# 04_DEBUG_DISPLAY.net
KiCad netlist of a schematic drawn in Altium Designer
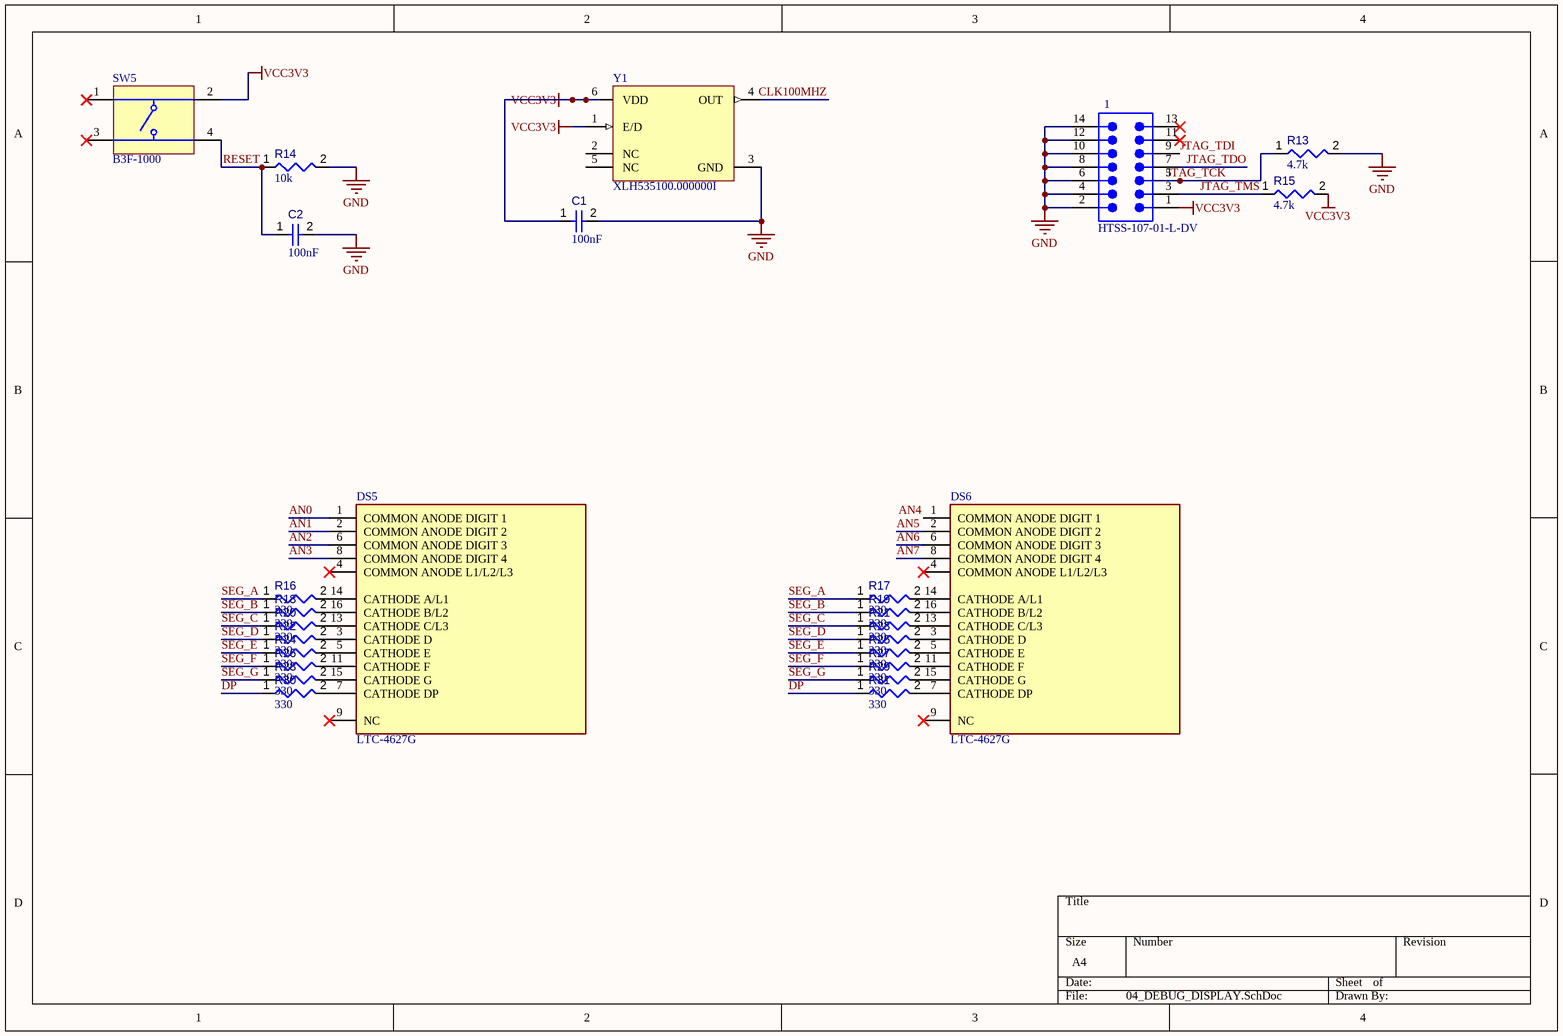
[diagram p0: 04_DEBUG_DISPLAY.SchDoc]

(export (version "E")
  (design (tool "Eeschema 10.0.6"))
  (components
    (comp (ref "1")
      (value "HTSS-107-01-L-DV")
      (footprint "SMTC-HTSS-107-01-X-DV")
      (fields (field (name "MANUFACTURER") "Samtec"))
      (libsource (lib "Altium Content Vault") (part "SMTC-HTSS-107-01-X-DV"))
    )
    (comp (ref "C1")
      (value "100nF")
      (footprint "CAPC0402(1005)60_L")
      (description "Chip Capacitor, 100nF +/-20%, 25V, 0402, Thickness 0.6 mm")
      (fields (field (name "TOLERANCE") "10%") (field (name "Comment") "Capacitor 100nF +/-20% 25V 0402"))
      (libsource (lib "Md-azadul Islam") (part "CAP-NP-2"))
    )
    (comp (ref "C2")
      (value "100nF")
      (footprint "CAPC0402(1005)60_L")
      (description "Chip Capacitor, 100nF +/-20%, 25V, 0402, Thickness 0.6 mm")
      (fields (field (name "TOLERANCE") "10%") (field (name "Comment") "Capacitor 100nF +/-20% 25V 0402"))
      (libsource (lib "Md-azadul Islam") (part "CAP-NP-2"))
    )
    (comp (ref "DS5")
      (value "LTC-4627G")
      (footprint "FP-LTC-4627G-MFG")
      (description "LED 7-SEG 4DIGIT GRN 0.4\" CA")
      (fields
        (field (name "OCTOPART") "https://octopart.com/ltc-4627g-lite-on-8442722")
        (field (name "MANUFACTURER") "Lite-On")
      )
      (libsource (lib "Altium Content Vault") (part "4d055b40ff5d7e2a8d2cf02d3223e38"))
    )
    (comp (ref "DS6")
      (value "LTC-4627G")
      (footprint "FP-LTC-4627G-MFG")
      (description "LED 7-SEG 4DIGIT GRN 0.4\" CA")
      (fields
        (field (name "OCTOPART") "https://octopart.com/ltc-4627g-lite-on-8442722")
        (field (name "MANUFACTURER") "Lite-On")
      )
      (libsource (lib "Altium Content Vault") (part "4d055b40ff5d7e2a8d2cf02d3223e38"))
    )
    (comp (ref "R13")
      (value "4.7k")
      (footprint "RESC0402(1005)_L")
      (description "Chip Resistor, 4,7 kOhms, +/-1 %, 63 mW, -55 to 155 degC, 0402")
      (fields (field (name "POWER") "63mW") (field (name "TOLERANCE") "1%"))
      (libsource (lib "Md-azadul Islam") (part "RES-2"))
    )
    (comp (ref "R14")
      (value "10k")
      (footprint "RESC0402(1005)_L")
      (description "10K 0.063W 1% 0402 (1005 Metric)  SMD")
      (fields (field (name "POWER") "63mW") (field (name "TOLERANCE") "1%"))
      (libsource (lib "Md-azadul Islam") (part "10KR2F"))
    )
    (comp (ref "R15")
      (value "4.7k")
      (footprint "RESC0402(1005)_L")
      (description "Chip Resistor, 4,7 kOhms, +/-1 %, 63 mW, -55 to 155 degC, 0402")
      (fields (field (name "POWER") "63mW") (field (name "TOLERANCE") "1%"))
      (libsource (lib "Md-azadul Islam") (part "RES-2"))
    )
    (comp (ref "R16")
      (value "330")
      (footprint "RESC0402(1005)_L")
      (description "330R 0.063W 5% 0402 (1005 Metric)  SMD")
      (fields (field (name "TOLERANCE") "5%") (field (name "POWER") "63mW"))
      (libsource (lib "Md-azadul Islam") (part "330R2J"))
    )
    (comp (ref "R17")
      (value "330")
      (footprint "RESC0402(1005)_L")
      (description "330R 0.063W 5% 0402 (1005 Metric)  SMD")
      (fields (field (name "TOLERANCE") "5%") (field (name "POWER") "63mW"))
      (libsource (lib "Md-azadul Islam") (part "330R2J"))
    )
    (comp (ref "R18")
      (value "330")
      (footprint "RESC0402(1005)_L")
      (description "330R 0.063W 5% 0402 (1005 Metric)  SMD")
      (fields (field (name "TOLERANCE") "5%") (field (name "POWER") "63mW"))
      (libsource (lib "Md-azadul Islam") (part "330R2J"))
    )
    (comp (ref "R19")
      (value "330")
      (footprint "RESC0402(1005)_L")
      (description "330R 0.063W 5% 0402 (1005 Metric)  SMD")
      (fields (field (name "TOLERANCE") "5%") (field (name "POWER") "63mW"))
      (libsource (lib "Md-azadul Islam") (part "330R2J"))
    )
    (comp (ref "R20")
      (value "330")
      (footprint "RESC0402(1005)_L")
      (description "330R 0.063W 5% 0402 (1005 Metric)  SMD")
      (fields (field (name "TOLERANCE") "5%") (field (name "POWER") "63mW"))
      (libsource (lib "Md-azadul Islam") (part "330R2J"))
    )
    (comp (ref "R21")
      (value "330")
      (footprint "RESC0402(1005)_L")
      (description "330R 0.063W 5% 0402 (1005 Metric)  SMD")
      (fields (field (name "TOLERANCE") "5%") (field (name "POWER") "63mW"))
      (libsource (lib "Md-azadul Islam") (part "330R2J"))
    )
    (comp (ref "R22")
      (value "330")
      (footprint "RESC0402(1005)_L")
      (description "330R 0.063W 5% 0402 (1005 Metric)  SMD")
      (fields (field (name "TOLERANCE") "5%") (field (name "POWER") "63mW"))
      (libsource (lib "Md-azadul Islam") (part "330R2J"))
    )
    (comp (ref "R23")
      (value "330")
      (footprint "RESC0402(1005)_L")
      (description "330R 0.063W 5% 0402 (1005 Metric)  SMD")
      (fields (field (name "TOLERANCE") "5%") (field (name "POWER") "63mW"))
      (libsource (lib "Md-azadul Islam") (part "330R2J"))
    )
    (comp (ref "R24")
      (value "330")
      (footprint "RESC0402(1005)_L")
      (description "330R 0.063W 5% 0402 (1005 Metric)  SMD")
      (fields (field (name "TOLERANCE") "5%") (field (name "POWER") "63mW"))
      (libsource (lib "Md-azadul Islam") (part "330R2J"))
    )
    (comp (ref "R25")
      (value "330")
      (footprint "RESC0402(1005)_L")
      (description "330R 0.063W 5% 0402 (1005 Metric)  SMD")
      (fields (field (name "TOLERANCE") "5%") (field (name "POWER") "63mW"))
      (libsource (lib "Md-azadul Islam") (part "330R2J"))
    )
    (comp (ref "R26")
      (value "330")
      (footprint "RESC0402(1005)_L")
      (description "330R 0.063W 5% 0402 (1005 Metric)  SMD")
      (fields (field (name "TOLERANCE") "5%") (field (name "POWER") "63mW"))
      (libsource (lib "Md-azadul Islam") (part "330R2J"))
    )
    (comp (ref "R27")
      (value "330")
      (footprint "RESC0402(1005)_L")
      (description "330R 0.063W 5% 0402 (1005 Metric)  SMD")
      (fields (field (name "TOLERANCE") "5%") (field (name "POWER") "63mW"))
      (libsource (lib "Md-azadul Islam") (part "330R2J"))
    )
    (comp (ref "R28")
      (value "330")
      (footprint "RESC0402(1005)_L")
      (description "330R 0.063W 5% 0402 (1005 Metric)  SMD")
      (fields (field (name "TOLERANCE") "5%") (field (name "POWER") "63mW"))
      (libsource (lib "Md-azadul Islam") (part "330R2J"))
    )
    (comp (ref "R29")
      (value "330")
      (footprint "RESC0402(1005)_L")
      (description "330R 0.063W 5% 0402 (1005 Metric)  SMD")
      (fields (field (name "TOLERANCE") "5%") (field (name "POWER") "63mW"))
      (libsource (lib "Md-azadul Islam") (part "330R2J"))
    )
    (comp (ref "R30")
      (value "330")
      (footprint "RESC0402(1005)_L")
      (description "330R 0.063W 5% 0402 (1005 Metric)  SMD")
      (fields (field (name "TOLERANCE") "5%") (field (name "POWER") "63mW"))
      (libsource (lib "Md-azadul Islam") (part "330R2J"))
    )
    (comp (ref "R31")
      (value "330")
      (footprint "RESC0402(1005)_L")
      (description "330R 0.063W 5% 0402 (1005 Metric)  SMD")
      (fields (field (name "TOLERANCE") "5%") (field (name "POWER") "63mW"))
      (libsource (lib "Md-azadul Islam") (part "330R2J"))
    )
    (comp (ref "SW5")
      (value "B3F-1000")
      (footprint "OMRON-B3F-1000-4_V")
      (description "Tactile Switch, SPST-NO, 0.05 A, 24 V, -25 to 70 degC, 4-Pin THD, RoHS, Bulk")
      (fields (field (name "MANUFACTURER") "Omron Electronic Components"))
      (libsource (lib "Md-azadul Islam") (part "SW-SPST-4_A"))
    )
    (comp (ref "Y1")
      (value "XLH535100.000000I")
      (footprint "JS6_MFG")
      (description "Oscillator Xo 100MHZ ±50PPM 15PF Lvcmos 60% 3.3V 6-PIN Cllcc SMD T/r")
      (libsource (lib "Altium Content Vault") (part "c6c94343aa228214f04837505267066"))
    )
  )
  (nets
    (net (code "1") (name "/  RESET") (class "Default")
      (node (ref "C2") (pin "1") (pinfunction "1_1") (pintype "passive"))
      (node (ref "R14") (pin "1") (pinfunction "1_1") (pintype "passive"))
      (node (ref "SW5") (pin "4") (pinfunction "4_4") (pintype "passive"))
    )
    (net (code "2") (name "/AN0") (class "Default")
      (node (ref "DS5") (pin "1") (pinfunction "COMMON_ANODE_DIGIT_1_1") (pintype "passive"))
    )
    (net (code "3") (name "/AN1") (class "Default")
      (node (ref "DS5") (pin "2") (pinfunction "COMMON_ANODE_DIGIT_2_2") (pintype "passive"))
    )
    (net (code "4") (name "/AN2") (class "Default")
      (node (ref "DS5") (pin "6") (pinfunction "COMMON_ANODE_DIGIT_3_6") (pintype "passive"))
    )
    (net (code "5") (name "/AN3") (class "Default")
      (node (ref "DS5") (pin "8") (pinfunction "COMMON_ANODE_DIGIT_4_8") (pintype "passive"))
    )
    (net (code "6") (name "/AN4") (class "Default")
      (node (ref "DS6") (pin "1") (pinfunction "COMMON_ANODE_DIGIT_1_1") (pintype "passive"))
    )
    (net (code "7") (name "/AN5") (class "Default")
      (node (ref "DS6") (pin "2") (pinfunction "COMMON_ANODE_DIGIT_2_2") (pintype "passive"))
    )
    (net (code "8") (name "/AN6") (class "Default")
      (node (ref "DS6") (pin "6") (pinfunction "COMMON_ANODE_DIGIT_3_6") (pintype "passive"))
    )
    (net (code "9") (name "/AN7") (class "Default")
      (node (ref "DS6") (pin "8") (pinfunction "COMMON_ANODE_DIGIT_4_8") (pintype "passive"))
    )
    (net (code "10") (name "/CLK100MHZ") (class "Default")
      (node (ref "Y1") (pin "4") (pinfunction "OUT_4") (pintype "output"))
    )
    (net (code "11") (name "/DP") (class "Default")
      (node (ref "R30") (pin "1") (pinfunction "1_1") (pintype "passive"))
      (node (ref "R31") (pin "1") (pinfunction "1_1") (pintype "passive"))
    )
    (net (code "12") (name "/JTAG_TCK") (class "Default")
      (node (ref "1") (pin "5") (pinfunction "5_5") (pintype "passive"))
      (node (ref "R13") (pin "1") (pinfunction "1_1") (pintype "passive"))
    )
    (net (code "13") (name "/JTAG_TDI") (class "Default")
      (node (ref "1") (pin "9") (pinfunction "9_9") (pintype "passive"))
    )
    (net (code "14") (name "/JTAG_TDO") (class "Default")
      (node (ref "1") (pin "7") (pinfunction "7_7") (pintype "passive"))
    )
    (net (code "15") (name "/JTAG_TMS") (class "Default")
      (node (ref "1") (pin "3") (pinfunction "3_3") (pintype "passive"))
      (node (ref "R15") (pin "1") (pinfunction "1_1") (pintype "passive"))
    )
    (net (code "16") (name "/SEG_A") (class "Default")
      (node (ref "R16") (pin "1") (pinfunction "1_1") (pintype "passive"))
      (node (ref "R17") (pin "1") (pinfunction "1_1") (pintype "passive"))
    )
    (net (code "17") (name "/SEG_B") (class "Default")
      (node (ref "R18") (pin "1") (pinfunction "1_1") (pintype "passive"))
      (node (ref "R19") (pin "1") (pinfunction "1_1") (pintype "passive"))
    )
    (net (code "18") (name "/SEG_C") (class "Default")
      (node (ref "R20") (pin "1") (pinfunction "1_1") (pintype "passive"))
      (node (ref "R21") (pin "1") (pinfunction "1_1") (pintype "passive"))
    )
    (net (code "19") (name "/SEG_D") (class "Default")
      (node (ref "R22") (pin "1") (pinfunction "1_1") (pintype "passive"))
      (node (ref "R23") (pin "1") (pinfunction "1_1") (pintype "passive"))
    )
    (net (code "20") (name "/SEG_E") (class "Default")
      (node (ref "R24") (pin "1") (pinfunction "1_1") (pintype "passive"))
      (node (ref "R25") (pin "1") (pinfunction "1_1") (pintype "passive"))
    )
    (net (code "21") (name "/SEG_F") (class "Default")
      (node (ref "R26") (pin "1") (pinfunction "1_1") (pintype "passive"))
      (node (ref "R27") (pin "1") (pinfunction "1_1") (pintype "passive"))
    )
    (net (code "22") (name "/SEG_G") (class "Default")
      (node (ref "R28") (pin "1") (pinfunction "1_1") (pintype "passive"))
      (node (ref "R29") (pin "1") (pinfunction "1_1") (pintype "passive"))
    )
    (net (code "23") (name "GND") (class "Default")
      (node (ref "1") (pin "10") (pinfunction "10_10") (pintype "passive"))
      (node (ref "1") (pin "12") (pinfunction "12_12") (pintype "passive"))
      (node (ref "1") (pin "14") (pinfunction "14_14") (pintype "passive"))
      (node (ref "1") (pin "2") (pinfunction "2_2") (pintype "passive"))
      (node (ref "1") (pin "4") (pinfunction "4_4") (pintype "passive"))
      (node (ref "1") (pin "6") (pinfunction "6_6") (pintype "passive"))
      (node (ref "1") (pin "8") (pinfunction "8_8") (pintype "passive"))
      (node (ref "C1") (pin "2") (pinfunction "2_2") (pintype "passive"))
      (node (ref "C2") (pin "2") (pinfunction "2_2") (pintype "passive"))
      (node (ref "R13") (pin "2") (pinfunction "2_2") (pintype "passive"))
      (node (ref "R14") (pin "2") (pinfunction "2_2") (pintype "passive"))
      (node (ref "Y1") (pin "3") (pinfunction "GND_3") (pintype "power_in"))
    )
    (net (code "24") (name "Net-(DS5-CATHODE_A{slash}L1)") (class "Default")
      (node (ref "DS5") (pin "14") (pinfunction "CATHODE_A/L1_14") (pintype "passive"))
      (node (ref "R16") (pin "2") (pinfunction "2_2") (pintype "passive"))
    )
    (net (code "25") (name "Net-(DS5-CATHODE_B{slash}L2)") (class "Default")
      (node (ref "DS5") (pin "16") (pinfunction "CATHODE_B/L2_16") (pintype "passive"))
      (node (ref "R18") (pin "2") (pinfunction "2_2") (pintype "passive"))
    )
    (net (code "26") (name "Net-(DS5-CATHODE_C{slash}L3)") (class "Default")
      (node (ref "DS5") (pin "13") (pinfunction "CATHODE_C/L3_13") (pintype "passive"))
      (node (ref "R20") (pin "2") (pinfunction "2_2") (pintype "passive"))
    )
    (net (code "27") (name "Net-(DS5-CATHODE_D)") (class "Default")
      (node (ref "DS5") (pin "3") (pinfunction "CATHODE_D_3") (pintype "passive"))
      (node (ref "R22") (pin "2") (pinfunction "2_2") (pintype "passive"))
    )
    (net (code "28") (name "Net-(DS5-CATHODE_DP)") (class "Default")
      (node (ref "DS5") (pin "7") (pinfunction "CATHODE_DP_7") (pintype "passive"))
      (node (ref "R30") (pin "2") (pinfunction "2_2") (pintype "passive"))
    )
    (net (code "29") (name "Net-(DS5-CATHODE_E)") (class "Default")
      (node (ref "DS5") (pin "5") (pinfunction "CATHODE_E_5") (pintype "passive"))
      (node (ref "R24") (pin "2") (pinfunction "2_2") (pintype "passive"))
    )
    (net (code "30") (name "Net-(DS5-CATHODE_F)") (class "Default")
      (node (ref "DS5") (pin "11") (pinfunction "CATHODE_F_11") (pintype "passive"))
      (node (ref "R26") (pin "2") (pinfunction "2_2") (pintype "passive"))
    )
    (net (code "31") (name "Net-(DS5-CATHODE_G)") (class "Default")
      (node (ref "DS5") (pin "15") (pinfunction "CATHODE_G_15") (pintype "passive"))
      (node (ref "R28") (pin "2") (pinfunction "2_2") (pintype "passive"))
    )
    (net (code "32") (name "Net-(DS6-CATHODE_A{slash}L1)") (class "Default")
      (node (ref "DS6") (pin "14") (pinfunction "CATHODE_A/L1_14") (pintype "passive"))
      (node (ref "R17") (pin "2") (pinfunction "2_2") (pintype "passive"))
    )
    (net (code "33") (name "Net-(DS6-CATHODE_B{slash}L2)") (class "Default")
      (node (ref "DS6") (pin "16") (pinfunction "CATHODE_B/L2_16") (pintype "passive"))
      (node (ref "R19") (pin "2") (pinfunction "2_2") (pintype "passive"))
    )
    (net (code "34") (name "Net-(DS6-CATHODE_C{slash}L3)") (class "Default")
      (node (ref "DS6") (pin "13") (pinfunction "CATHODE_C/L3_13") (pintype "passive"))
      (node (ref "R21") (pin "2") (pinfunction "2_2") (pintype "passive"))
    )
    (net (code "35") (name "Net-(DS6-CATHODE_D)") (class "Default")
      (node (ref "DS6") (pin "3") (pinfunction "CATHODE_D_3") (pintype "passive"))
      (node (ref "R23") (pin "2") (pinfunction "2_2") (pintype "passive"))
    )
    (net (code "36") (name "Net-(DS6-CATHODE_DP)") (class "Default")
      (node (ref "DS6") (pin "7") (pinfunction "CATHODE_DP_7") (pintype "passive"))
      (node (ref "R31") (pin "2") (pinfunction "2_2") (pintype "passive"))
    )
    (net (code "37") (name "Net-(DS6-CATHODE_E)") (class "Default")
      (node (ref "DS6") (pin "5") (pinfunction "CATHODE_E_5") (pintype "passive"))
      (node (ref "R25") (pin "2") (pinfunction "2_2") (pintype "passive"))
    )
    (net (code "38") (name "Net-(DS6-CATHODE_F)") (class "Default")
      (node (ref "DS6") (pin "11") (pinfunction "CATHODE_F_11") (pintype "passive"))
      (node (ref "R27") (pin "2") (pinfunction "2_2") (pintype "passive"))
    )
    (net (code "39") (name "Net-(DS6-CATHODE_G)") (class "Default")
      (node (ref "DS6") (pin "15") (pinfunction "CATHODE_G_15") (pintype "passive"))
      (node (ref "R29") (pin "2") (pinfunction "2_2") (pintype "passive"))
    )
    (net (code "40") (name "VCC3V3") (class "Default")
      (node (ref "1") (pin "1") (pinfunction "1_1") (pintype "passive"))
      (node (ref "C1") (pin "1") (pinfunction "1_1") (pintype "passive"))
      (node (ref "R15") (pin "2") (pinfunction "2_2") (pintype "passive"))
      (node (ref "SW5") (pin "2") (pinfunction "2_2") (pintype "passive"))
      (node (ref "Y1") (pin "1") (pinfunction "E/D_1") (pintype "input"))
      (node (ref "Y1") (pin "6") (pinfunction "VDD_6") (pintype "power_in"))
    )
    (net (code "41") (name "unconnected-(1-Pad11)") (class "Default")
      (node (ref "1") (pin "11") (pinfunction "11_11") (pintype "passive+no_connect"))
    )
    (net (code "42") (name "unconnected-(1-Pad13)") (class "Default")
      (node (ref "1") (pin "13") (pinfunction "13_13") (pintype "passive+no_connect"))
    )
    (net (code "43") (name "unconnected-(DS5-COMMON_ANODE_L1{slash}L2{slash}L3-Pad4)") (class "Default")
      (node (ref "DS5") (pin "4") (pinfunction "COMMON_ANODE_L1/L2/L3_4") (pintype "passive+no_connect"))
    )
    (net (code "44") (name "unconnected-(DS5-NC-Pad9)") (class "Default")
      (node (ref "DS5") (pin "9") (pinfunction "NC_9") (pintype "passive+no_connect"))
    )
    (net (code "45") (name "unconnected-(DS6-COMMON_ANODE_L1{slash}L2{slash}L3-Pad4)") (class "Default")
      (node (ref "DS6") (pin "4") (pinfunction "COMMON_ANODE_L1/L2/L3_4") (pintype "passive+no_connect"))
    )
    (net (code "46") (name "unconnected-(DS6-NC-Pad9)") (class "Default")
      (node (ref "DS6") (pin "9") (pinfunction "NC_9") (pintype "passive+no_connect"))
    )
    (net (code "47") (name "unconnected-(SW5-Pad1)") (class "Default")
      (node (ref "SW5") (pin "1") (pinfunction "1_1") (pintype "passive+no_connect"))
    )
    (net (code "48") (name "unconnected-(SW5-Pad3)") (class "Default")
      (node (ref "SW5") (pin "3") (pinfunction "3_3") (pintype "passive+no_connect"))
    )
    (net (code "49") (name "unconnected-(Y1-NC-Pad2)") (class "Default")
      (node (ref "Y1") (pin "2") (pinfunction "NC_2") (pintype "passive"))
    )
    (net (code "50") (name "unconnected-(Y1-NC-Pad5)") (class "Default")
      (node (ref "Y1") (pin "5") (pinfunction "NC_5") (pintype "passive"))
    )
  )
)
